# GPS.net
KiCad netlist of a schematic drawn in Altium Designer
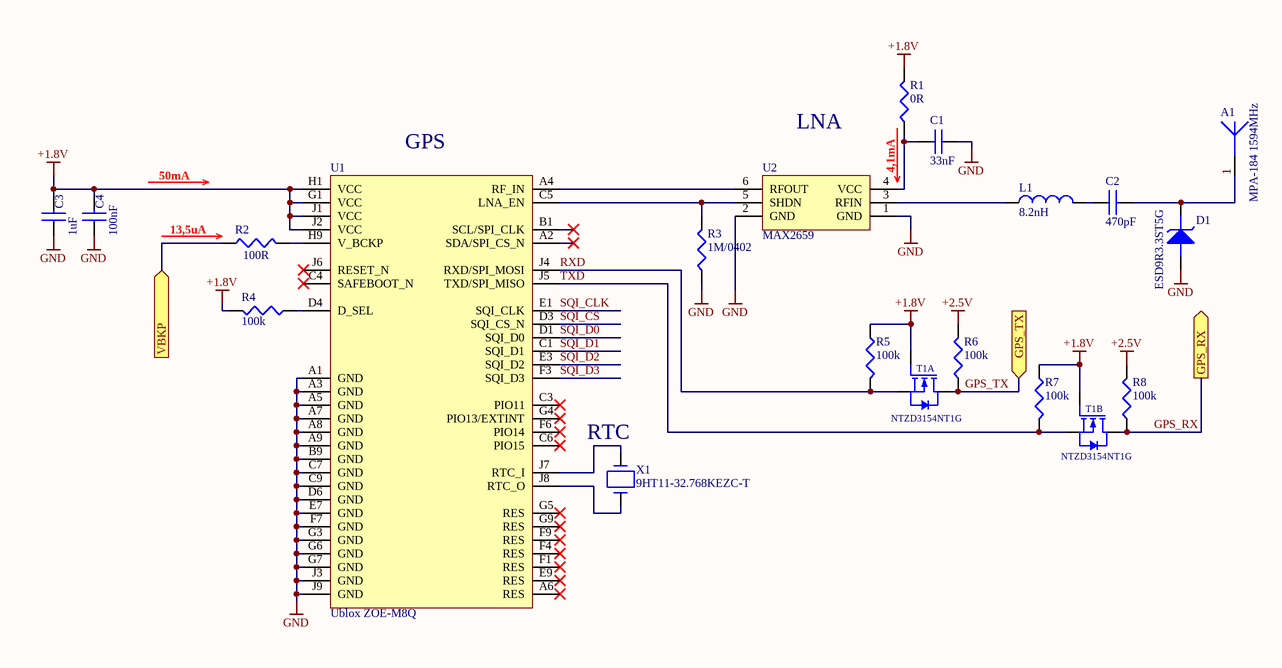
[diagram p0: GPS.SchDoc]

(export (version "E")
  (design (tool "Eeschema 10.0.6"))
  (components
    (comp (ref "A1")
      (value "MPA-184 1594MHz")
      (footprint "MPA-184")
      (description "Antennas Passive GPS/GLONASS Patch Antenna")
      (fields (field (name "MANUFACTURER") "Antenova") (field (name "MANUFACTURER PART NUMBER") "SR42I010-R"))
      (libsource (lib "Passive") (part "ANT - MAXTENA MPA-184 1594MHz"))
    )
    (comp (ref "C1")
      (value "33nF")
      (footprint "CAP0402")
      (description "33 pF, 16 V,  5%, C0G / NP0, MC Series")
      (fields
        (field (name "MANUFACTURER") "Multicomp")
        (field (name "MANUFACTURER PART NUMBER") "MC0402N330J160CT")
      )
      (libsource (lib "Passive") (part "C - 33pF/0402"))
    )
    (comp (ref "C2")
      (value "470pF")
      (footprint "CAP0402")
      (description "470 pF, 50 V, 0402 [1005 Metric], ± 10%, X7R, GRT Series")
      (fields
        (field (name "MANUFACTURER") "Murata")
        (field (name "MANUFACTURER PART NUMBER") "GRT155R71H471KE01D")
      )
      (libsource (lib "Passive") (part "C - 470pF/0402"))
    )
    (comp (ref "C3")
      (value "1uF")
      (footprint "CAP0402")
      (description "CAP CER 1UF 10V 20% X5R 0402")
      (fields
        (field (name "MANUFACTURER") "Murata")
        (field (name "MANUFACTURER PART NUMBER") "GRM155R61A105ME15D")
      )
      (libsource (lib "Passive") (part "C - 1uF/0402"))
    )
    (comp (ref "C4")
      (value "100nF")
      (footprint "CAP0402")
      (description "0.1 F, 16 V,  5%, X5R, MC Series")
      (fields
        (field (name "MANUFACTURER") "Multicomp")
        (field (name "MANUFACTURER PART NUMBER") "MC0402X104J160CT")
      )
      (libsource (lib "Passive") (part "C - 100nF/0402"))
    )
    (comp (ref "D1")
      (value "ESD9R3.3ST5G")
      (footprint "SOD-923")
      (description "TVS Diode, ESD9R Series, Unidirectional, 3.3 V, 7.8 V")
      (fields
        (field (name "MANUFACTURER") "DIODES INC.")
        (field (name "MANUFACTURER PART NUMBER") "1N4148W-7-F.")
      )
      (libsource (lib "Active") (part "D_TVS - ESD9R3.3ST5G"))
    )
    (comp (ref "L1")
      (value "8.2nH")
      (footprint "IND0402")
      (description "High Frequency Inductor, 8.2 nH, LQG15HN Series, 300 mA, 0402 [1005 Metric], Multilayer, 0.33 ohm")
      (fields
        (field (name "MANUFACTURER") "Murata")
        (field (name "MANUFACTURER PART NUMBER") "LQG15HS33NJ02D")
      )
      (libsource (lib "Passive") (part "L - 33nH/0402"))
    )
    (comp (ref "R1")
      (value "0R")
      (footprint "RES0402")
      (description "RESISTOR, 0402, 0R, ANTI SULFURATION")
      (fields
        (field (name "MANUFACTURER") "Multicomp")
        (field (name "MANUFACTURER PART NUMBER") "MCMR04X000PTL")
      )
      (libsource (lib "Passive") (part "R - 0R/0402"))
    )
    (comp (ref "R2")
      (value "100R")
      (footprint "RES0402")
      (description "100 ohm, 50 V, 0402 [1005 Metric], 62.5 mW,  1%")
      (fields
        (field (name "MANUFACTURER") "Multicomp")
        (field (name "MANUFACTURER PART NUMBER") "MCMR04X1000FTL")
      )
      (libsource (lib "Passive") (part "R - 100R/0402"))
    )
    (comp (ref "R3")
      (value "1M/0402")
      (footprint "RES0402")
      (description "MCMR04X1004FTL RES, 1M, 1%, 0.0625W, 0402, THICK FILM")
      (fields
        (field (name "MANUFACTURER") "MULTICOMP")
        (field (name "MANUFACTURER PART NUMBER") "MC0063W060311M")
      )
      (libsource (lib "Passive") (part "R - 1M/0402"))
    )
    (comp (ref "R4")
      (value "100k")
      (footprint "RES0402")
      (description "100KOHM, 1%, 0.0625W")
      (fields
        (field (name "MANUFACTURER") "Multicomp")
        (field (name "MANUFACTURER PART NUMBER") "MCWR04X1003FTL")
      )
      (libsource (lib "Passive") (part "R - 100k/0402"))
    )
    (comp (ref "R5")
      (value "100k")
      (footprint "RES0402")
      (description "100KOHM, 1%, 0.0625W")
      (fields
        (field (name "MANUFACTURER") "Multicomp")
        (field (name "MANUFACTURER PART NUMBER") "MCWR04X1003FTL")
      )
      (libsource (lib "Passive") (part "R - 100k/0402"))
    )
    (comp (ref "R6")
      (value "100k")
      (footprint "RES0402")
      (description "100KOHM, 1%, 0.0625W")
      (fields
        (field (name "MANUFACTURER") "Multicomp")
        (field (name "MANUFACTURER PART NUMBER") "MCWR04X1003FTL")
      )
      (libsource (lib "Passive") (part "R - 100k/0402"))
    )
    (comp (ref "R7")
      (value "100k")
      (footprint "RES0402")
      (description "100KOHM, 1%, 0.0625W")
      (fields
        (field (name "MANUFACTURER") "Multicomp")
        (field (name "MANUFACTURER PART NUMBER") "MCWR04X1003FTL")
      )
      (libsource (lib "Passive") (part "R - 100k/0402"))
    )
    (comp (ref "R8")
      (value "100k")
      (footprint "RES0402")
      (description "100KOHM, 1%, 0.0625W")
      (fields
        (field (name "MANUFACTURER") "Multicomp")
        (field (name "MANUFACTURER PART NUMBER") "MCWR04X1003FTL")
      )
      (libsource (lib "Passive") (part "R - 100k/0402"))
    )
    (comp (ref "T1")
      (value "NTZD3154NT1G")
      (footprint "SOT-563")
      (description "Dual MOSFET, Dual N Channel, 540 mA, 20 V, 0.4 ohm, 4.5 V, 1 V")
      (fields (field (name "AUTHOR") "Ciril Golob"))
      (libsource (lib "Active") (part "T_M - NTZD3154NT1G"))
    )
    (comp (ref "U1")
      (value "Ublox ZOE-M8Q")
      (footprint "S-LGA51")
      (description "ZOE-M8 RF Receiver BeiDou, Galileo, GLONASS, GNSS, GPS -160dBm")
      (fields (field (name "MANUFACTURER") "u-blox") (field (name "MANUFACTURER PART NUMBER") "MAX-M8Q-0"))
      (libsource (lib "Active") (part "RF - UBLOX-ZOE-M8B"))
    )
    (comp (ref "U2")
      (value "MAX2659")
      (footprint "uDFN-6")
      (description "RF Amplifier, GPS / GNSS, 20.5 dB Gain / 0.8 dB Noise, 1575.42 MHz, 1.6 V to 3.3 V Supply")
      (fields (field (name "MANUFACTURER") "u-blox") (field (name "MANUFACTURER PART NUMBER") "MAX-M8Q-0"))
      (libsource (lib "Active") (part "RF - MAX2659"))
    )
    (comp (ref "X1")
      (value "9HT11-32.768KEZC-T")
      (footprint "9HT11")
      (description "Crystal, 32.768 kHz, SMD, 2mm x 1.2mm, 9 pF, 10 ppm, 9HT11 Series")
      (fields (field (name "MANUFACTURER") "IQD") (field (name "MANUFACTURER PART NUMBER") "LFXTAL009678"))
      (libsource (lib "Passive") (part "X - 9HT11-32.768KEZC-T"))
    )
  )
  (nets
    (net (code "1") (name "+1.8V") (class "Default")
      (node (ref "C3") (pin "2") (pinfunction "2_2") (pintype "passive"))
      (node (ref "C4") (pin "2") (pinfunction "2_2") (pintype "passive"))
      (node (ref "R1") (pin "2") (pinfunction "2_2") (pintype "passive"))
      (node (ref "R4") (pin "2") (pinfunction "2_2") (pintype "passive"))
      (node (ref "R5") (pin "1") (pinfunction "1_1") (pintype "passive"))
      (node (ref "R7") (pin "1") (pinfunction "1_1") (pintype "passive"))
      (node (ref "T1") (pin "2") (pinfunction "G1_2") (pintype "passive"))
      (node (ref "T1") (pin "5") (pinfunction "G2_5") (pintype "passive"))
      (node (ref "U1") (pin "G1") (pinfunction "VCC_G1") (pintype "passive"))
      (node (ref "U1") (pin "H1") (pinfunction "VCC_H1") (pintype "passive"))
      (node (ref "U1") (pin "J1") (pinfunction "VCC_J1") (pintype "passive"))
      (node (ref "U1") (pin "J2") (pinfunction "VCC_J2") (pintype "passive"))
    )
    (net (code "2") (name "+2.5V") (class "Default")
      (node (ref "R6") (pin "2") (pinfunction "2_2") (pintype "passive"))
      (node (ref "R8") (pin "2") (pinfunction "2_2") (pintype "passive"))
    )
    (net (code "3") (name "/GPS_RX") (class "Default")
      (node (ref "R8") (pin "1") (pinfunction "1_1") (pintype "passive"))
      (node (ref "T1") (pin "3") (pinfunction "D2_3") (pintype "passive"))
    )
    (net (code "4") (name "/GPS_TX") (class "Default")
      (node (ref "R6") (pin "1") (pinfunction "1_1") (pintype "passive"))
      (node (ref "T1") (pin "6") (pinfunction "D1_6") (pintype "passive"))
    )
    (net (code "5") (name "/RXD") (class "Default")
      (node (ref "R5") (pin "2") (pinfunction "2_2") (pintype "passive"))
      (node (ref "T1") (pin "1") (pinfunction "S1_1") (pintype "passive"))
      (node (ref "U1") (pin "J4") (pinfunction "RXD/SPI_MOSI_J4") (pintype "passive"))
    )
    (net (code "6") (name "/SQI_CLK") (class "Default")
      (node (ref "U1") (pin "E1") (pinfunction "SQI_CLK_E1") (pintype "passive"))
    )
    (net (code "7") (name "/SQI_CS") (class "Default")
      (node (ref "U1") (pin "D3") (pinfunction "SQI_CS_N_D3") (pintype "passive"))
    )
    (net (code "8") (name "/SQI_D0") (class "Default")
      (node (ref "U1") (pin "D1") (pinfunction "SQI_D0_D1") (pintype "passive"))
    )
    (net (code "9") (name "/SQI_D1") (class "Default")
      (node (ref "U1") (pin "C1") (pinfunction "SQI_D1_C1") (pintype "passive"))
    )
    (net (code "10") (name "/SQI_D2") (class "Default")
      (node (ref "U1") (pin "E3") (pinfunction "SQI_D2_E3") (pintype "passive"))
    )
    (net (code "11") (name "/SQI_D3") (class "Default")
      (node (ref "U1") (pin "F3") (pinfunction "SQI_D3_F3") (pintype "passive"))
    )
    (net (code "12") (name "/TXD") (class "Default")
      (node (ref "R7") (pin "2") (pinfunction "2_2") (pintype "passive"))
      (node (ref "T1") (pin "4") (pinfunction "S2_4") (pintype "passive"))
      (node (ref "U1") (pin "J5") (pinfunction "TXD/SPI_MISO_J5") (pintype "passive"))
    )
    (net (code "13") (name "/VBKP") (class "Default")
      (node (ref "R2") (pin "1") (pinfunction "1_1") (pintype "passive"))
    )
    (net (code "14") (name "GND") (class "Default")
      (node (ref "C1") (pin "1") (pinfunction "1_1") (pintype "passive"))
      (node (ref "C3") (pin "1") (pinfunction "1_1") (pintype "passive"))
      (node (ref "C4") (pin "1") (pinfunction "1_1") (pintype "passive"))
      (node (ref "D1") (pin "A") (pinfunction "ANODE_A") (pintype "passive"))
      (node (ref "R3") (pin "1") (pinfunction "1_1") (pintype "passive"))
      (node (ref "U1") (pin "A1") (pinfunction "GND_A1") (pintype "passive"))
      (node (ref "U1") (pin "A3") (pinfunction "GND_A3") (pintype "passive"))
      (node (ref "U1") (pin "A5") (pinfunction "GND_A5") (pintype "passive"))
      (node (ref "U1") (pin "A7") (pinfunction "GND_A7") (pintype "passive"))
      (node (ref "U1") (pin "A8") (pinfunction "GND_A8") (pintype "passive"))
      (node (ref "U1") (pin "A9") (pinfunction "GND_A9") (pintype "passive"))
      (node (ref "U1") (pin "B9") (pinfunction "GND_B9") (pintype "passive"))
      (node (ref "U1") (pin "C7") (pinfunction "GND_C7") (pintype "passive"))
      (node (ref "U1") (pin "C9") (pinfunction "GND_C9") (pintype "passive"))
      (node (ref "U1") (pin "D6") (pinfunction "GND_D6") (pintype "passive"))
      (node (ref "U1") (pin "E7") (pinfunction "GND_E7") (pintype "passive"))
      (node (ref "U1") (pin "F7") (pinfunction "GND_F7") (pintype "passive"))
      (node (ref "U1") (pin "G3") (pinfunction "GND_G3") (pintype "passive"))
      (node (ref "U1") (pin "G6") (pinfunction "GND_G6") (pintype "passive"))
      (node (ref "U1") (pin "G7") (pinfunction "GND_G7") (pintype "passive"))
      (node (ref "U1") (pin "J3") (pinfunction "GND_J3") (pintype "passive"))
      (node (ref "U1") (pin "J9") (pinfunction "GND_J9") (pintype "passive"))
      (node (ref "U2") (pin "1") (pinfunction "GND_1") (pintype "passive"))
      (node (ref "U2") (pin "2") (pinfunction "GND_2") (pintype "passive"))
    )
    (net (code "15") (name "Net-(A1-ANT)") (class "Default")
      (node (ref "A1") (pin "1") (pinfunction "ANT_1") (pintype "passive"))
      (node (ref "C2") (pin "2") (pinfunction "2_2") (pintype "passive"))
      (node (ref "D1") (pin "K") (pinfunction "cathode_K") (pintype "passive"))
    )
    (net (code "16") (name "Net-(C2-Pad1)") (class "Default")
      (node (ref "C2") (pin "1") (pinfunction "1_1") (pintype "passive"))
      (node (ref "L1") (pin "2") (pinfunction "2_2") (pintype "passive"))
    )
    (net (code "17") (name "Net-(U1-D_SEL)") (class "Default")
      (node (ref "R4") (pin "1") (pinfunction "1_1") (pintype "passive"))
      (node (ref "U1") (pin "D4") (pinfunction "D_SEL_D4") (pintype "passive"))
    )
    (net (code "18") (name "Net-(U1-LNA_EN)") (class "Default")
      (node (ref "R3") (pin "2") (pinfunction "2_2") (pintype "passive"))
      (node (ref "U1") (pin "C5") (pinfunction "LNA_EN_C5") (pintype "passive"))
      (node (ref "U2") (pin "5") (pinfunction "SHDN_5") (pintype "passive"))
    )
    (net (code "19") (name "Net-(U1-RF_IN)") (class "Default")
      (node (ref "U1") (pin "A4") (pinfunction "RF_IN_A4") (pintype "passive"))
      (node (ref "U2") (pin "6") (pinfunction "RFOUT_6") (pintype "passive"))
    )
    (net (code "20") (name "Net-(U1-RTC_I)") (class "Default")
      (node (ref "U1") (pin "J7") (pinfunction "RTC_I_J7") (pintype "passive"))
      (node (ref "X1") (pin "2") (pinfunction "2_2") (pintype "passive"))
    )
    (net (code "21") (name "Net-(U1-RTC_O)") (class "Default")
      (node (ref "U1") (pin "J8") (pinfunction "RTC_O_J8") (pintype "passive"))
      (node (ref "X1") (pin "1") (pinfunction "1_1") (pintype "passive"))
    )
    (net (code "22") (name "Net-(U1-V_BCKP)") (class "Default")
      (node (ref "R2") (pin "2") (pinfunction "2_2") (pintype "passive"))
      (node (ref "U1") (pin "H9") (pinfunction "V_BCKP_H9") (pintype "passive"))
    )
    (net (code "23") (name "Net-(U2-RFIN)") (class "Default")
      (node (ref "L1") (pin "1") (pinfunction "1_1") (pintype "passive"))
      (node (ref "U2") (pin "3") (pinfunction "RFIN_3") (pintype "passive"))
    )
    (net (code "24") (name "Net-(U2-VCC)") (class "Default")
      (node (ref "C1") (pin "2") (pinfunction "2_2") (pintype "passive"))
      (node (ref "R1") (pin "1") (pinfunction "1_1") (pintype "passive"))
      (node (ref "U2") (pin "4") (pinfunction "VCC_4") (pintype "passive"))
    )
    (net (code "25") (name "unconnected-(U1-PIO11-PadC3)") (class "Default")
      (node (ref "U1") (pin "C3") (pinfunction "PIO11_C3") (pintype "passive+no_connect"))
    )
    (net (code "26") (name "unconnected-(U1-PIO13{slash}EXTINT-PadG4)") (class "Default")
      (node (ref "U1") (pin "G4") (pinfunction "PIO13/EXTINT_G4") (pintype "passive+no_connect"))
    )
    (net (code "27") (name "unconnected-(U1-PIO14-PadF6)") (class "Default")
      (node (ref "U1") (pin "F6") (pinfunction "PIO14_F6") (pintype "passive+no_connect"))
    )
    (net (code "28") (name "unconnected-(U1-PIO15-PadC6)") (class "Default")
      (node (ref "U1") (pin "C6") (pinfunction "PIO15_C6") (pintype "passive+no_connect"))
    )
    (net (code "29") (name "unconnected-(U1-RES-PadA6)") (class "Default")
      (node (ref "U1") (pin "A6") (pinfunction "RES_A6") (pintype "passive+no_connect"))
    )
    (net (code "30") (name "unconnected-(U1-RES-PadE9)") (class "Default")
      (node (ref "U1") (pin "E9") (pinfunction "RES_E9") (pintype "passive+no_connect"))
    )
    (net (code "31") (name "unconnected-(U1-RES-PadF1)") (class "Default")
      (node (ref "U1") (pin "F1") (pinfunction "RES_F1") (pintype "passive+no_connect"))
    )
    (net (code "32") (name "unconnected-(U1-RES-PadF4)") (class "Default")
      (node (ref "U1") (pin "F4") (pinfunction "RES_F4") (pintype "passive+no_connect"))
    )
    (net (code "33") (name "unconnected-(U1-RES-PadF9)") (class "Default")
      (node (ref "U1") (pin "F9") (pinfunction "RES_F9") (pintype "passive+no_connect"))
    )
    (net (code "34") (name "unconnected-(U1-RES-PadG5)") (class "Default")
      (node (ref "U1") (pin "G5") (pinfunction "RES_G5") (pintype "passive+no_connect"))
    )
    (net (code "35") (name "unconnected-(U1-RES-PadG9)") (class "Default")
      (node (ref "U1") (pin "G9") (pinfunction "RES_G9") (pintype "passive+no_connect"))
    )
    (net (code "36") (name "unconnected-(U1-RESET_N-PadJ6)") (class "Default")
      (node (ref "U1") (pin "J6") (pinfunction "RESET_N_J6") (pintype "passive+no_connect"))
    )
    (net (code "37") (name "unconnected-(U1-SAFEBOOT_N-PadC4)") (class "Default")
      (node (ref "U1") (pin "C4") (pinfunction "SAFEBOOT_N_C4") (pintype "passive+no_connect"))
    )
    (net (code "38") (name "unconnected-(U1-SCL{slash}SPI_CLK-PadB1)") (class "Default")
      (node (ref "U1") (pin "B1") (pinfunction "SCL/SPI_CLK_B1") (pintype "passive+no_connect"))
    )
    (net (code "39") (name "unconnected-(U1-SDA{slash}SPI_CS_N-PadA2)") (class "Default")
      (node (ref "U1") (pin "A2") (pinfunction "SDA/SPI_CS_N_A2") (pintype "passive+no_connect"))
    )
  )
)
